# micron_ram.net
KiCad netlist of a schematic drawn in Altium Designer
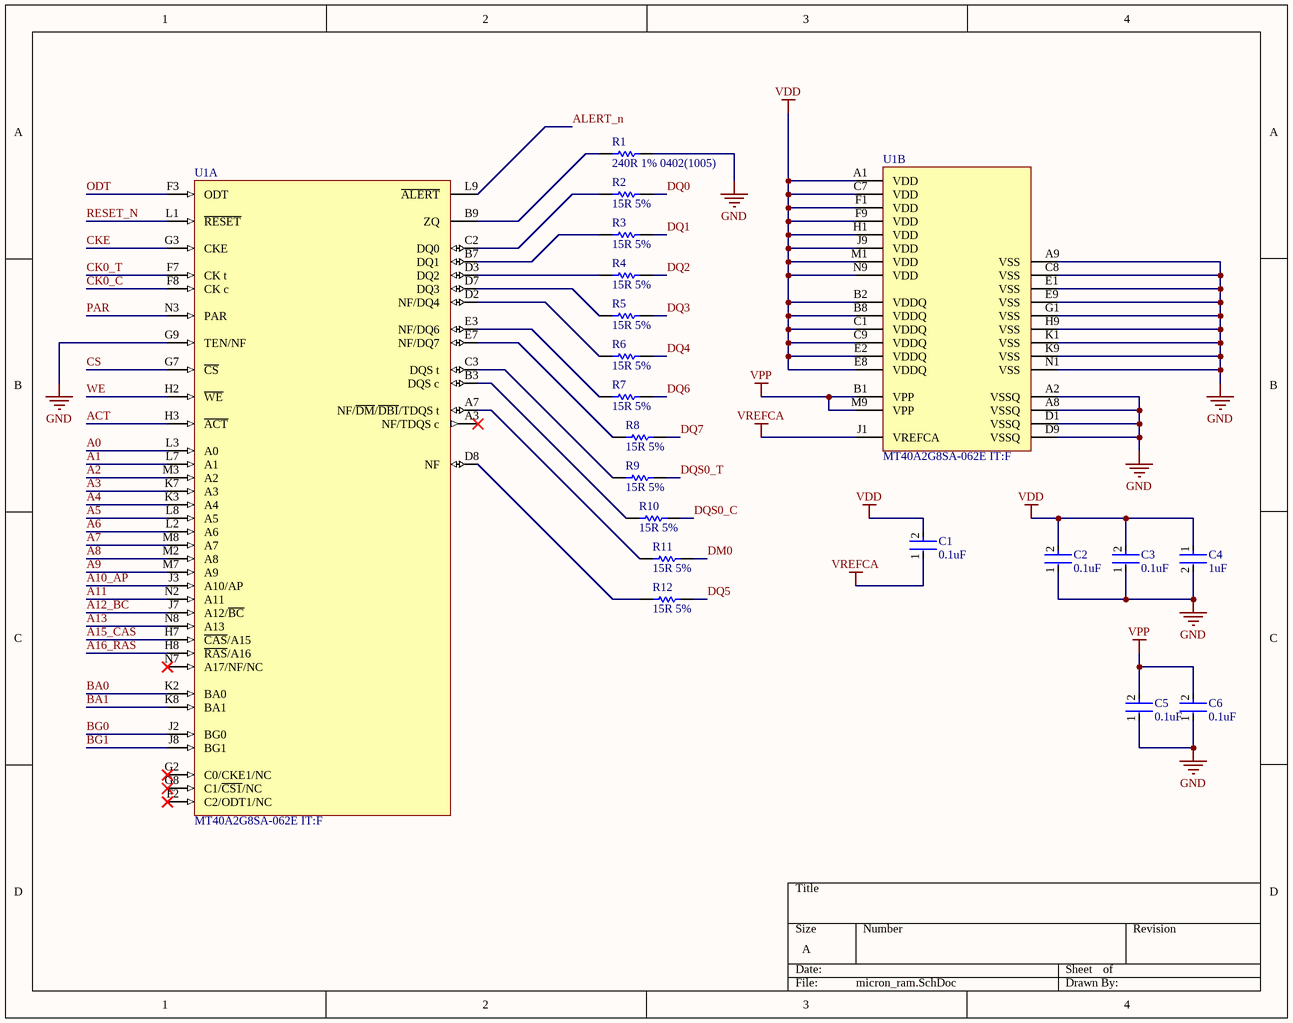
[diagram p0: micron_ram.SchDoc]

(export (version "E")
  (design (tool "Eeschema 10.0.6"))
  (components
    (comp (ref "C1")
      (value "0.1uF")
      (footprint "FP-GRM15-MFG")
      (description "CAP CER 0.1UF 16V X7R 0402")
      (fields (field (name "MANUFACTURER PART NUMBER") "GRM155R71C104KA88D") (field (name "TOLERANCE") "10%"))
      (libsource (lib "Altium Content Vault") (part "236180d848d6139a670b325ea6854c9"))
    )
    (comp (ref "C2")
      (value "0.1uF")
      (footprint "FP-GRM15-MFG")
      (description "CAP CER 0.1UF 16V X7R 0402")
      (fields (field (name "MANUFACTURER PART NUMBER") "GRM155R71C104KA88D") (field (name "TOLERANCE") "10%"))
      (libsource (lib "Altium Content Vault") (part "236180d848d6139a670b325ea6854c9"))
    )
    (comp (ref "C3")
      (value "0.1uF")
      (footprint "FP-GRM15-MFG")
      (description "CAP CER 0.1UF 16V X7R 0402")
      (fields (field (name "MANUFACTURER PART NUMBER") "GRM155R71C104KA88D") (field (name "TOLERANCE") "10%"))
      (libsource (lib "Altium Content Vault") (part "236180d848d6139a670b325ea6854c9"))
    )
    (comp (ref "C4")
      (value "1uF")
      (footprint "FP-CL511-IPC_C")
      (description "Cap Ceramic 1uF 10V X5R ±10% SMD 0402 +85°C Paper T/R")
      (fields (field (name "TOLERANCE") "10%"))
      (libsource (lib "Altium Content Vault") (part "b4654b650e69147ec39a6b967a45e02"))
    )
    (comp (ref "C5")
      (value "0.1uF")
      (footprint "FP-GRM15-MFG")
      (description "CAP CER 0.1UF 16V X7R 0402")
      (fields (field (name "MANUFACTURER PART NUMBER") "GRM155R71C104KA88D") (field (name "TOLERANCE") "10%"))
      (libsource (lib "Altium Content Vault") (part "236180d848d6139a670b325ea6854c9"))
    )
    (comp (ref "C6")
      (value "0.1uF")
      (footprint "FP-GRM15-MFG")
      (description "CAP CER 0.1UF 16V X7R 0402")
      (fields (field (name "MANUFACTURER PART NUMBER") "GRM155R71C104KA88D") (field (name "TOLERANCE") "10%"))
      (libsource (lib "Altium Content Vault") (part "236180d848d6139a670b325ea6854c9"))
    )
    (comp (ref "R1")
      (value "240R 1% 0402(1005)")
      (footprint "RESC0402(1005)_L")
      (description "240R 0.063W 1% 0402 (1005 Metric)  SMD")
      (fields (field (name "POWER") "0.063 W") (field (name "TOLERANCE") "1 %"))
      (libsource (lib "Altium Content Vault") (part "RES"))
    )
    (comp (ref "R2")
      (value "15R 5%")
      (footprint "RESC1005X40X25LL05T10")
      (fields (field (name "MANUFACTURER") "Yageo / Phycomp") (field (name "PART NUMBER") "RC0402FR-0715RL"))
      (libsource (lib "Altium Content Vault") (part "RES"))
    )
    (comp (ref "R3")
      (value "15R 5%")
      (footprint "RESC1005X40X25LL05T10")
      (fields (field (name "MANUFACTURER") "Yageo / Phycomp") (field (name "PART NUMBER") "RC0402FR-0715RL"))
      (libsource (lib "Altium Content Vault") (part "RES"))
    )
    (comp (ref "R4")
      (value "15R 5%")
      (footprint "RESC1005X40X25LL05T10")
      (fields (field (name "MANUFACTURER") "Yageo / Phycomp") (field (name "PART NUMBER") "RC0402FR-0715RL"))
      (libsource (lib "Altium Content Vault") (part "RES"))
    )
    (comp (ref "R5")
      (value "15R 5%")
      (footprint "RESC1005X40X25LL05T10")
      (fields (field (name "MANUFACTURER") "Yageo / Phycomp") (field (name "PART NUMBER") "RC0402FR-0715RL"))
      (libsource (lib "Altium Content Vault") (part "RES"))
    )
    (comp (ref "R6")
      (value "15R 5%")
      (footprint "RESC1005X40X25LL05T10")
      (fields (field (name "MANUFACTURER") "Yageo / Phycomp") (field (name "PART NUMBER") "RC0402FR-0715RL"))
      (libsource (lib "Altium Content Vault") (part "RES"))
    )
    (comp (ref "R7")
      (value "15R 5%")
      (footprint "RESC1005X40X25LL05T10")
      (fields (field (name "MANUFACTURER") "Yageo / Phycomp") (field (name "PART NUMBER") "RC0402FR-0715RL"))
      (libsource (lib "Altium Content Vault") (part "RES"))
    )
    (comp (ref "R8")
      (value "15R 5%")
      (footprint "RESC1005X40X25LL05T10")
      (fields (field (name "MANUFACTURER") "Yageo / Phycomp") (field (name "PART NUMBER") "RC0402FR-0715RL"))
      (libsource (lib "Altium Content Vault") (part "RES"))
    )
    (comp (ref "R9")
      (value "15R 5%")
      (footprint "RESC1005X40X25LL05T10")
      (fields (field (name "MANUFACTURER") "Yageo / Phycomp") (field (name "PART NUMBER") "RC0402FR-0715RL"))
      (libsource (lib "Altium Content Vault") (part "RES"))
    )
    (comp (ref "R10")
      (value "15R 5%")
      (footprint "RESC1005X40X25LL05T10")
      (fields (field (name "MANUFACTURER") "Yageo / Phycomp") (field (name "PART NUMBER") "RC0402FR-0715RL"))
      (libsource (lib "Altium Content Vault") (part "RES"))
    )
    (comp (ref "R11")
      (value "15R 5%")
      (footprint "RESC1005X40X25LL05T10")
      (fields (field (name "MANUFACTURER") "Yageo / Phycomp") (field (name "PART NUMBER") "RC0402FR-0715RL"))
      (libsource (lib "Altium Content Vault") (part "RES"))
    )
    (comp (ref "R12")
      (value "15R 5%")
      (footprint "RESC1005X40X25LL05T10")
      (fields (field (name "MANUFACTURER") "Yageo / Phycomp") (field (name "PART NUMBER") "RC0402FR-0715RL"))
      (libsource (lib "Altium Content Vault") (part "RES"))
    )
    (comp (ref "U1")
      (value "MT40A2G8SA-062E IT:F")
      (footprint "SA_MFG")
      (description "DRAMChip DDR4 SDRAM 16Gbit 2Gx8 1.2V 78-Pin FBGA Tray")
      (libsource (lib "Altium Content Vault") (part "d28cb998757b614ee3280f10a38a3b1"))
    )
  )
  (nets
    (net (code "1") (name "/A0") (class "Default")
      (node (ref "U1") (pin "L3") (pinfunction "A0_L3") (pintype "input"))
    )
    (net (code "2") (name "/A1") (class "Default")
      (node (ref "U1") (pin "L7") (pinfunction "A1_L7") (pintype "input"))
    )
    (net (code "3") (name "/A2") (class "Default")
      (node (ref "U1") (pin "M3") (pinfunction "A2_M3") (pintype "input"))
    )
    (net (code "4") (name "/A3") (class "Default")
      (node (ref "U1") (pin "K7") (pinfunction "A3_K7") (pintype "input"))
    )
    (net (code "5") (name "/A4") (class "Default")
      (node (ref "U1") (pin "K3") (pinfunction "A4_K3") (pintype "input"))
    )
    (net (code "6") (name "/A5") (class "Default")
      (node (ref "U1") (pin "L8") (pinfunction "A5_L8") (pintype "input"))
    )
    (net (code "7") (name "/A6") (class "Default")
      (node (ref "U1") (pin "L2") (pinfunction "A6_L2") (pintype "input"))
    )
    (net (code "8") (name "/A7") (class "Default")
      (node (ref "U1") (pin "M8") (pinfunction "A7_M8") (pintype "input"))
    )
    (net (code "9") (name "/A8") (class "Default")
      (node (ref "U1") (pin "M2") (pinfunction "A8_M2") (pintype "input"))
    )
    (net (code "10") (name "/A9") (class "Default")
      (node (ref "U1") (pin "M7") (pinfunction "A9_M7") (pintype "input"))
    )
    (net (code "11") (name "/A10_AP") (class "Default")
      (node (ref "U1") (pin "J3") (pinfunction "A10/AP_J3") (pintype "input"))
    )
    (net (code "12") (name "/A11") (class "Default")
      (node (ref "U1") (pin "N2") (pinfunction "A11_N2") (pintype "input"))
    )
    (net (code "13") (name "/A12_BC") (class "Default")
      (node (ref "U1") (pin "J7") (pinfunction "A12/~{BC}_J7") (pintype "input"))
    )
    (net (code "14") (name "/A13") (class "Default")
      (node (ref "U1") (pin "N8") (pinfunction "A13_N8") (pintype "input"))
    )
    (net (code "15") (name "/A15_CAS") (class "Default")
      (node (ref "U1") (pin "H7") (pinfunction "~{CAS}/A15_H7") (pintype "input"))
    )
    (net (code "16") (name "/A16_RAS") (class "Default")
      (node (ref "U1") (pin "H8") (pinfunction "~{RAS}/A16_H8") (pintype "input"))
    )
    (net (code "17") (name "/ACT") (class "Default")
      (node (ref "U1") (pin "H3") (pinfunction "~{ACT}_H3") (pintype "input"))
    )
    (net (code "18") (name "/ALERT_n") (class "Default")
      (node (ref "U1") (pin "L9") (pinfunction "~{ALERT}_L9") (pintype "open_collector"))
    )
    (net (code "19") (name "/BA0") (class "Default")
      (node (ref "U1") (pin "K2") (pinfunction "BA0_K2") (pintype "input"))
    )
    (net (code "20") (name "/BA1") (class "Default")
      (node (ref "U1") (pin "K8") (pinfunction "BA1_K8") (pintype "input"))
    )
    (net (code "21") (name "/BG0") (class "Default")
      (node (ref "U1") (pin "J2") (pinfunction "BG0_J2") (pintype "input"))
    )
    (net (code "22") (name "/BG1") (class "Default")
      (node (ref "U1") (pin "J8") (pinfunction "BG1_J8") (pintype "input"))
    )
    (net (code "23") (name "/CK0_C") (class "Default")
      (node (ref "U1") (pin "F8") (pinfunction "CK_c_F8") (pintype "input"))
    )
    (net (code "24") (name "/CK0_T") (class "Default")
      (node (ref "U1") (pin "F7") (pinfunction "CK_t_F7") (pintype "input"))
    )
    (net (code "25") (name "/CKE") (class "Default")
      (node (ref "U1") (pin "G3") (pinfunction "CKE_G3") (pintype "input"))
    )
    (net (code "26") (name "/CS") (class "Default")
      (node (ref "U1") (pin "G7") (pinfunction "~{CS}_G7") (pintype "input"))
    )
    (net (code "27") (name "/DM0") (class "Default")
      (node (ref "R11") (pin "2") (pinfunction "2_2") (pintype "passive"))
    )
    (net (code "28") (name "/DQ0") (class "Default")
      (node (ref "R2") (pin "2") (pinfunction "2_2") (pintype "passive"))
    )
    (net (code "29") (name "/DQ1") (class "Default")
      (node (ref "R3") (pin "2") (pinfunction "2_2") (pintype "passive"))
    )
    (net (code "30") (name "/DQ2") (class "Default")
      (node (ref "R4") (pin "2") (pinfunction "2_2") (pintype "passive"))
    )
    (net (code "31") (name "/DQ3") (class "Default")
      (node (ref "R5") (pin "2") (pinfunction "2_2") (pintype "passive"))
    )
    (net (code "32") (name "/DQ4") (class "Default")
      (node (ref "R6") (pin "2") (pinfunction "2_2") (pintype "passive"))
    )
    (net (code "33") (name "/DQ5") (class "Default")
      (node (ref "R12") (pin "2") (pinfunction "2_2") (pintype "passive"))
    )
    (net (code "34") (name "/DQ6") (class "Default")
      (node (ref "R7") (pin "2") (pinfunction "2_2") (pintype "passive"))
    )
    (net (code "35") (name "/DQ7") (class "Default")
      (node (ref "R8") (pin "2") (pinfunction "2_2") (pintype "passive"))
    )
    (net (code "36") (name "/DQS0_C") (class "Default")
      (node (ref "R10") (pin "2") (pinfunction "2_2") (pintype "passive"))
    )
    (net (code "37") (name "/DQS0_T") (class "Default")
      (node (ref "R9") (pin "2") (pinfunction "2_2") (pintype "passive"))
    )
    (net (code "38") (name "/ODT") (class "Default")
      (node (ref "U1") (pin "F3") (pinfunction "ODT_F3") (pintype "input"))
    )
    (net (code "39") (name "/PAR") (class "Default")
      (node (ref "U1") (pin "N3") (pinfunction "PAR_N3") (pintype "input"))
    )
    (net (code "40") (name "/RESET_N") (class "Default")
      (node (ref "U1") (pin "L1") (pinfunction "~{RESET}_L1") (pintype "input"))
    )
    (net (code "41") (name "/WE") (class "Default")
      (node (ref "U1") (pin "H2") (pinfunction "~{WE}_H2") (pintype "input"))
    )
    (net (code "42") (name "GND") (class "Default")
      (node (ref "C2") (pin "1") (pinfunction "1_1") (pintype "passive"))
      (node (ref "C3") (pin "1") (pinfunction "1_1") (pintype "passive"))
      (node (ref "C4") (pin "2") (pinfunction "2_2") (pintype "passive"))
      (node (ref "C5") (pin "1") (pinfunction "1_1") (pintype "passive"))
      (node (ref "C6") (pin "1") (pinfunction "1_1") (pintype "passive"))
      (node (ref "R1") (pin "2") (pinfunction "2_2") (pintype "passive"))
      (node (ref "U1") (pin "A2") (pinfunction "VSSQ_A2") (pintype "power_in"))
      (node (ref "U1") (pin "A8") (pinfunction "VSSQ_A8") (pintype "power_in"))
      (node (ref "U1") (pin "A9") (pinfunction "VSS_A9") (pintype "power_in"))
      (node (ref "U1") (pin "C8") (pinfunction "VSS_C8") (pintype "power_in"))
      (node (ref "U1") (pin "D1") (pinfunction "VSSQ_D1") (pintype "power_in"))
      (node (ref "U1") (pin "D9") (pinfunction "VSSQ_D9") (pintype "power_in"))
      (node (ref "U1") (pin "E1") (pinfunction "VSS_E1") (pintype "power_in"))
      (node (ref "U1") (pin "E9") (pinfunction "VSS_E9") (pintype "power_in"))
      (node (ref "U1") (pin "G1") (pinfunction "VSS_G1") (pintype "power_in"))
      (node (ref "U1") (pin "G9") (pinfunction "TEN/NF_G9") (pintype "input"))
      (node (ref "U1") (pin "H9") (pinfunction "VSS_H9") (pintype "power_in"))
      (node (ref "U1") (pin "K1") (pinfunction "VSS_K1") (pintype "power_in"))
      (node (ref "U1") (pin "K9") (pinfunction "VSS_K9") (pintype "power_in"))
      (node (ref "U1") (pin "N1") (pinfunction "VSS_N1") (pintype "power_in"))
    )
    (net (code "43") (name "Net-(U1A-DQ0)") (class "Default")
      (node (ref "R2") (pin "1") (pinfunction "1_1") (pintype "passive"))
      (node (ref "U1") (pin "C2") (pinfunction "DQ0_C2") (pintype "bidirectional"))
    )
    (net (code "44") (name "Net-(U1A-DQ1)") (class "Default")
      (node (ref "R3") (pin "1") (pinfunction "1_1") (pintype "passive"))
      (node (ref "U1") (pin "B7") (pinfunction "DQ1_B7") (pintype "bidirectional"))
    )
    (net (code "45") (name "Net-(U1A-DQ2)") (class "Default")
      (node (ref "R4") (pin "1") (pinfunction "1_1") (pintype "passive"))
      (node (ref "U1") (pin "D3") (pinfunction "DQ2_D3") (pintype "bidirectional"))
    )
    (net (code "46") (name "Net-(U1A-DQ3)") (class "Default")
      (node (ref "R5") (pin "1") (pinfunction "1_1") (pintype "passive"))
      (node (ref "U1") (pin "D7") (pinfunction "DQ3_D7") (pintype "bidirectional"))
    )
    (net (code "47") (name "Net-(U1A-DQS_c)") (class "Default")
      (node (ref "R10") (pin "1") (pinfunction "1_1") (pintype "passive"))
      (node (ref "U1") (pin "B3") (pinfunction "DQS_c_B3") (pintype "bidirectional"))
    )
    (net (code "48") (name "Net-(U1A-DQS_t)") (class "Default")
      (node (ref "R9") (pin "1") (pinfunction "1_1") (pintype "passive"))
      (node (ref "U1") (pin "C3") (pinfunction "DQS_t_C3") (pintype "bidirectional"))
    )
    (net (code "49") (name "Net-(U1A-NF)") (class "Default")
      (node (ref "R12") (pin "1") (pinfunction "1_1") (pintype "passive"))
      (node (ref "U1") (pin "D8") (pinfunction "NF_D8") (pintype "bidirectional"))
    )
    (net (code "50") (name "Net-(U1A-NF{slash}DQ4)") (class "Default")
      (node (ref "R6") (pin "1") (pinfunction "1_1") (pintype "passive"))
      (node (ref "U1") (pin "D2") (pinfunction "NF/DQ4_D2") (pintype "bidirectional"))
    )
    (net (code "51") (name "Net-(U1A-NF{slash}DQ6)") (class "Default")
      (node (ref "R7") (pin "1") (pinfunction "1_1") (pintype "passive"))
      (node (ref "U1") (pin "E3") (pinfunction "NF/DQ6_E3") (pintype "bidirectional"))
    )
    (net (code "52") (name "Net-(U1A-NF{slash}DQ7)") (class "Default")
      (node (ref "R8") (pin "1") (pinfunction "1_1") (pintype "passive"))
      (node (ref "U1") (pin "E7") (pinfunction "NF/DQ7_E7") (pintype "bidirectional"))
    )
    (net (code "53") (name "Net-(U1A-NF{slash}~{DM}{slash}~{DBI}{slash}TDQS_t)") (class "Default")
      (node (ref "R11") (pin "1") (pinfunction "1_1") (pintype "passive"))
      (node (ref "U1") (pin "A7") (pinfunction "NF/~{DM}/~{DBI}/TDQS_t_A7") (pintype "bidirectional"))
    )
    (net (code "54") (name "Net-(U1A-ZQ)") (class "Default")
      (node (ref "R1") (pin "1") (pinfunction "1_1") (pintype "passive"))
      (node (ref "U1") (pin "B9") (pinfunction "ZQ_B9") (pintype "passive"))
    )
    (net (code "55") (name "VDD") (class "Default")
      (node (ref "C1") (pin "2") (pinfunction "2_2") (pintype "passive"))
      (node (ref "C2") (pin "2") (pinfunction "2_2") (pintype "passive"))
      (node (ref "C3") (pin "2") (pinfunction "2_2") (pintype "passive"))
      (node (ref "C4") (pin "1") (pinfunction "1_1") (pintype "passive"))
      (node (ref "U1") (pin "A1") (pinfunction "VDD_A1") (pintype "power_in"))
      (node (ref "U1") (pin "B2") (pinfunction "VDDQ_B2") (pintype "power_in"))
      (node (ref "U1") (pin "B8") (pinfunction "VDDQ_B8") (pintype "power_in"))
      (node (ref "U1") (pin "C1") (pinfunction "VDDQ_C1") (pintype "power_in"))
      (node (ref "U1") (pin "C7") (pinfunction "VDD_C7") (pintype "power_in"))
      (node (ref "U1") (pin "C9") (pinfunction "VDDQ_C9") (pintype "power_in"))
      (node (ref "U1") (pin "E2") (pinfunction "VDDQ_E2") (pintype "power_in"))
      (node (ref "U1") (pin "E8") (pinfunction "VDDQ_E8") (pintype "power_in"))
      (node (ref "U1") (pin "F1") (pinfunction "VDD_F1") (pintype "power_in"))
      (node (ref "U1") (pin "F9") (pinfunction "VDD_F9") (pintype "power_in"))
      (node (ref "U1") (pin "H1") (pinfunction "VDD_H1") (pintype "power_in"))
      (node (ref "U1") (pin "J9") (pinfunction "VDD_J9") (pintype "power_in"))
      (node (ref "U1") (pin "M1") (pinfunction "VDD_M1") (pintype "power_in"))
      (node (ref "U1") (pin "N9") (pinfunction "VDD_N9") (pintype "power_in"))
    )
    (net (code "56") (name "VPP") (class "Default")
      (node (ref "C5") (pin "2") (pinfunction "2_2") (pintype "passive"))
      (node (ref "C6") (pin "2") (pinfunction "2_2") (pintype "passive"))
      (node (ref "U1") (pin "B1") (pinfunction "VPP_B1") (pintype "power_in"))
      (node (ref "U1") (pin "M9") (pinfunction "VPP_M9") (pintype "power_in"))
    )
    (net (code "57") (name "VREFCA") (class "Default")
      (node (ref "C1") (pin "1") (pinfunction "1_1") (pintype "passive"))
      (node (ref "U1") (pin "J1") (pinfunction "VREFCA_J1") (pintype "power_in"))
    )
    (net (code "58") (name "unconnected-(U1A-A17{slash}NF{slash}NC-PadN7)") (class "Default")
      (node (ref "U1") (pin "N7") (pinfunction "A17/NF/NC_N7") (pintype "input+no_connect"))
    )
    (net (code "59") (name "unconnected-(U1A-C0{slash}CKE1{slash}NC-PadG2)") (class "Default")
      (node (ref "U1") (pin "G2") (pinfunction "C0/CKE1/NC_G2") (pintype "input+no_connect"))
    )
    (net (code "60") (name "unconnected-(U1A-C1{slash}~{CS1}{slash}NC-PadG8)") (class "Default")
      (node (ref "U1") (pin "G8") (pinfunction "C1/~{CS1}/NC_G8") (pintype "input+no_connect"))
    )
    (net (code "61") (name "unconnected-(U1A-C2{slash}ODT1{slash}NC-PadF2)") (class "Default")
      (node (ref "U1") (pin "F2") (pinfunction "C2/ODT1/NC_F2") (pintype "input+no_connect"))
    )
    (net (code "62") (name "unconnected-(U1A-NF{slash}TDQS_c-PadA3)") (class "Default")
      (node (ref "U1") (pin "A3") (pinfunction "NF/TDQS_c_A3") (pintype "output+no_connect"))
    )
  )
)
